# shield.net
KiCad netlist of a schematic drawn in EAGLE
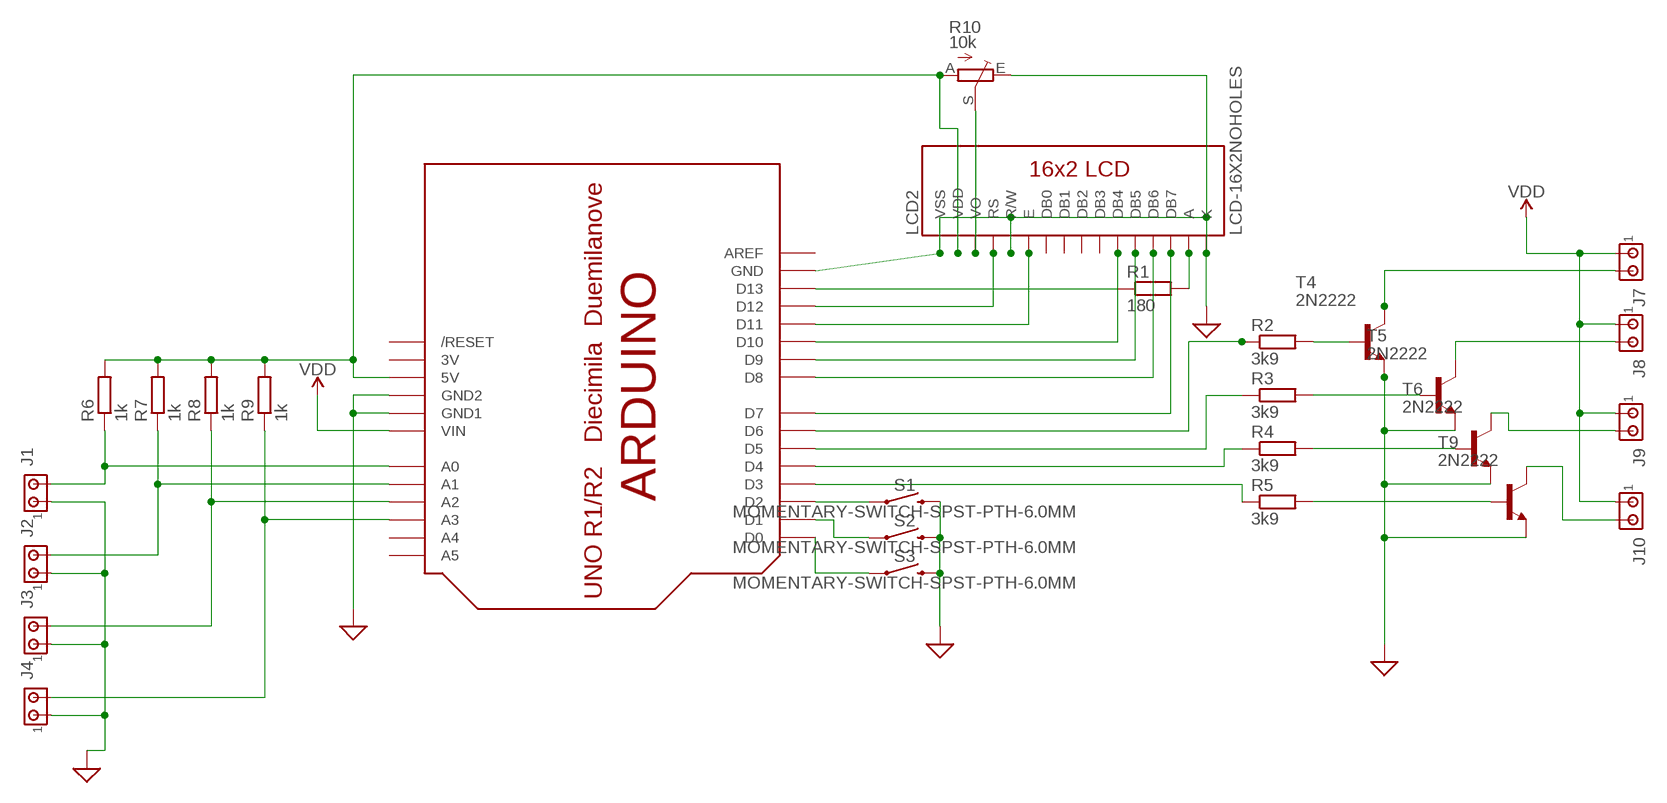
[diagram p0: schematic, sheet 1]

(export (version "E")
  (design (tool "Eeschema 10.0.6"))
  (components
    (comp (ref "J1")
      (value "MTA02-100")
      (footprint "eagle-import:10X02MTA")
      (libsource (lib "eagle-import") (part "MTA02-100"))
    )
    (comp (ref "J2")
      (value "MTA02-100")
      (footprint "eagle-import:10X02MTA")
      (libsource (lib "eagle-import") (part "MTA02-100"))
    )
    (comp (ref "J3")
      (value "MTA02-100")
      (footprint "eagle-import:10X02MTA")
      (libsource (lib "eagle-import") (part "MTA02-100"))
    )
    (comp (ref "J4")
      (value "MTA02-100")
      (footprint "eagle-import:10X02MTA")
      (libsource (lib "eagle-import") (part "MTA02-100"))
    )
    (comp (ref "J7")
      (value "MTA02-100")
      (footprint "eagle-import:10X02MTA")
      (libsource (lib "eagle-import") (part "MTA02-100"))
    )
    (comp (ref "J8")
      (value "MTA02-100")
      (footprint "eagle-import:10X02MTA")
      (libsource (lib "eagle-import") (part "MTA02-100"))
    )
    (comp (ref "J9")
      (value "MTA02-100")
      (footprint "eagle-import:10X02MTA")
      (libsource (lib "eagle-import") (part "MTA02-100"))
    )
    (comp (ref "J10")
      (value "MTA02-100")
      (footprint "eagle-import:10X02MTA")
      (libsource (lib "eagle-import") (part "MTA02-100"))
    )
    (comp (ref "LCD2")
      (value "LCD-16X2NOHOLES")
      (footprint "eagle-import:LCD-16X2_NOHOLESNOSILK")
      (libsource (lib "eagle-import") (part "LCD-16X2NOHOLES"))
    )
    (comp (ref "R1")
      (value "180")
      (footprint "eagle-import:0207_10")
      (libsource (lib "eagle-import") (part "R-EU_0207/10"))
    )
    (comp (ref "R2")
      (value "3k9")
      (footprint "eagle-import:0207_10")
      (libsource (lib "eagle-import") (part "R-EU_0207/10"))
    )
    (comp (ref "R3")
      (value "3k9")
      (footprint "eagle-import:0207_10")
      (libsource (lib "eagle-import") (part "R-EU_0207/10"))
    )
    (comp (ref "R4")
      (value "3k9")
      (footprint "eagle-import:0207_10")
      (libsource (lib "eagle-import") (part "R-EU_0207/10"))
    )
    (comp (ref "R5")
      (value "3k9")
      (footprint "eagle-import:0207_10")
      (libsource (lib "eagle-import") (part "R-EU_0207/10"))
    )
    (comp (ref "R6")
      (value "1k")
      (footprint "eagle-import:0207_10")
      (libsource (lib "eagle-import") (part "R-EU_0207/10"))
    )
    (comp (ref "R7")
      (value "1k")
      (footprint "eagle-import:0207_10")
      (libsource (lib "eagle-import") (part "R-EU_0207/10"))
    )
    (comp (ref "R8")
      (value "1k")
      (footprint "eagle-import:0207_10")
      (libsource (lib "eagle-import") (part "R-EU_0207/10"))
    )
    (comp (ref "R9")
      (value "1k")
      (footprint "eagle-import:0207_10")
      (libsource (lib "eagle-import") (part "R-EU_0207/10"))
    )
    (comp (ref "R10")
      (value "10k")
      (footprint "eagle-import:B25P")
      (libsource (lib "eagle-import") (part "TRIM_EU-B25P"))
    )
    (comp (ref "S1")
      (value "MOMENTARY-SWITCH-SPST-PTH-6.0MM")
      (footprint "eagle-import:TACTILE_SWITCH_PTH_6.0MM")
      (libsource (lib "eagle-import") (part "MOMENTARY-SWITCH-SPST-PTH-6.0MM"))
    )
    (comp (ref "S2")
      (value "MOMENTARY-SWITCH-SPST-PTH-6.0MM")
      (footprint "eagle-import:TACTILE_SWITCH_PTH_6.0MM")
      (libsource (lib "eagle-import") (part "MOMENTARY-SWITCH-SPST-PTH-6.0MM"))
    )
    (comp (ref "S3")
      (value "MOMENTARY-SWITCH-SPST-PTH-6.0MM")
      (footprint "eagle-import:TACTILE_SWITCH_PTH_6.0MM")
      (libsource (lib "eagle-import") (part "MOMENTARY-SWITCH-SPST-PTH-6.0MM"))
    )
    (comp (ref "T4")
      (value "2N2222")
      (footprint "eagle-import:TO92-EBC-OVAL")
      (libsource (lib "eagle-import") (part "2N2222"))
    )
    (comp (ref "T5")
      (value "2N2222")
      (footprint "eagle-import:TO92-EBC-OVAL")
      (libsource (lib "eagle-import") (part "2N2222"))
    )
    (comp (ref "T6")
      (value "2N2222")
      (footprint "eagle-import:TO92-EBC-OVAL")
      (libsource (lib "eagle-import") (part "2N2222"))
    )
    (comp (ref "T9")
      (value "2N2222")
      (footprint "eagle-import:TO92-EBC-OVAL")
      (libsource (lib "eagle-import") (part "2N2222"))
    )
    (comp (ref "U$1")
      (value "ARDUINO-NOHOLE")
      (footprint "eagle-import:ARDUINO-NOHOLE")
      (libsource (lib "eagle-import") (part "ARDUINO-NOHOLE"))
    )
  )
  (nets
    (net (code "1") (name "/3V") (class "Default")
      (node (ref "U$1") (pin "3V") (pinfunction "3V_3V") (pintype "power_in"))
    )
    (net (code "2") (name "Net-(J1-Pad2)") (class "Default")
      (node (ref "J1") (pin "2") (pinfunction "2_2") (pintype "passive"))
      (node (ref "R6") (pin "1") (pinfunction "1_1") (pintype "passive"))
      (node (ref "U$1") (pin "A0") (pinfunction "A0_A0") (pintype "bidirectional"))
    )
    (net (code "3") (name "Net-(J2-Pad2)") (class "Default")
      (node (ref "J2") (pin "2") (pinfunction "2_2") (pintype "passive"))
      (node (ref "R7") (pin "1") (pinfunction "1_1") (pintype "passive"))
      (node (ref "U$1") (pin "A1") (pinfunction "A1_A1") (pintype "bidirectional"))
    )
    (net (code "4") (name "Net-(J3-Pad2)") (class "Default")
      (node (ref "J3") (pin "2") (pinfunction "2_2") (pintype "passive"))
      (node (ref "R8") (pin "1") (pinfunction "1_1") (pintype "passive"))
      (node (ref "U$1") (pin "A2") (pinfunction "A2_A2") (pintype "bidirectional"))
    )
    (net (code "5") (name "Net-(J4-Pad2)") (class "Default")
      (node (ref "J4") (pin "2") (pinfunction "2_2") (pintype "passive"))
      (node (ref "R9") (pin "1") (pinfunction "1_1") (pintype "passive"))
      (node (ref "U$1") (pin "A3") (pinfunction "A3_A3") (pintype "bidirectional"))
    )
    (net (code "6") (name "Net-(J7-Pad2)") (class "Default")
      (node (ref "J7") (pin "2") (pinfunction "2_2") (pintype "passive"))
      (node (ref "T4") (pin "C") (pinfunction "C_C") (pintype "passive"))
    )
    (net (code "7") (name "Net-(J8-Pad2)") (class "Default")
      (node (ref "J8") (pin "2") (pinfunction "2_2") (pintype "passive"))
      (node (ref "T5") (pin "C") (pinfunction "C_C") (pintype "passive"))
    )
    (net (code "8") (name "Net-(J9-Pad2)") (class "Default")
      (node (ref "J9") (pin "2") (pinfunction "2_2") (pintype "passive"))
      (node (ref "T6") (pin "C") (pinfunction "C_C") (pintype "passive"))
    )
    (net (code "9") (name "Net-(J10-Pad2)") (class "Default")
      (node (ref "J10") (pin "2") (pinfunction "2_2") (pintype "passive"))
      (node (ref "T9") (pin "C") (pinfunction "C_C") (pintype "passive"))
    )
    (net (code "10") (name "Net-(LCD2-A)") (class "Default")
      (node (ref "LCD2") (pin "15") (pinfunction "A_15") (pintype "power_in"))
      (node (ref "R1") (pin "2") (pinfunction "2_2") (pintype "passive"))
    )
    (net (code "11") (name "Net-(LCD2-DB4)") (class "Default")
      (node (ref "LCD2") (pin "11") (pinfunction "DB4_11") (pintype "bidirectional"))
      (node (ref "U$1") (pin "D10") (pinfunction "D10_D10") (pintype "bidirectional"))
    )
    (net (code "12") (name "Net-(LCD2-DB5)") (class "Default")
      (node (ref "LCD2") (pin "12") (pinfunction "DB5_12") (pintype "bidirectional"))
      (node (ref "U$1") (pin "D9") (pinfunction "D9_D9") (pintype "bidirectional"))
    )
    (net (code "13") (name "Net-(LCD2-DB6)") (class "Default")
      (node (ref "LCD2") (pin "13") (pinfunction "DB6_13") (pintype "bidirectional"))
      (node (ref "U$1") (pin "D8") (pinfunction "D8_D8") (pintype "bidirectional"))
    )
    (net (code "14") (name "Net-(LCD2-DB7)") (class "Default")
      (node (ref "LCD2") (pin "14") (pinfunction "DB7_14") (pintype "bidirectional"))
      (node (ref "U$1") (pin "D7") (pinfunction "D7_D7") (pintype "bidirectional"))
    )
    (net (code "15") (name "Net-(LCD2-E)") (class "Default")
      (node (ref "LCD2") (pin "6") (pinfunction "E_6") (pintype "input"))
      (node (ref "U$1") (pin "D11") (pinfunction "D11_D11") (pintype "bidirectional"))
    )
    (net (code "16") (name "Net-(LCD2-RS)") (class "Default")
      (node (ref "LCD2") (pin "4") (pinfunction "RS_4") (pintype "input"))
      (node (ref "U$1") (pin "D12") (pinfunction "D12_D12") (pintype "bidirectional"))
    )
    (net (code "17") (name "Net-(LCD2-VDD)") (class "Default")
      (node (ref "LCD2") (pin "2") (pinfunction "VDD_2") (pintype "power_in"))
      (node (ref "R10") (pin "A") (pinfunction "A_A") (pintype "passive"))
      (node (ref "R6") (pin "2") (pinfunction "2_2") (pintype "passive"))
      (node (ref "R7") (pin "2") (pinfunction "2_2") (pintype "passive"))
      (node (ref "R8") (pin "2") (pinfunction "2_2") (pintype "passive"))
      (node (ref "R9") (pin "2") (pinfunction "2_2") (pintype "passive"))
      (node (ref "U$1") (pin "5V") (pinfunction "5V_5V") (pintype "power_in"))
    )
    (net (code "18") (name "Net-(LCD2-VO)") (class "Default")
      (node (ref "LCD2") (pin "3") (pinfunction "VO_3") (pintype "bidirectional"))
      (node (ref "R10") (pin "S") (pinfunction "S_S") (pintype "passive"))
    )
    (net (code "19") (name "Net-(R1-Pad1)") (class "Default")
      (node (ref "R1") (pin "1") (pinfunction "1_1") (pintype "passive"))
      (node (ref "U$1") (pin "D13") (pinfunction "D13_D13") (pintype "bidirectional"))
    )
    (net (code "20") (name "Net-(R2-Pad1)") (class "Default")
      (node (ref "R2") (pin "1") (pinfunction "1_1") (pintype "passive"))
      (node (ref "U$1") (pin "D6") (pinfunction "D6_D6") (pintype "bidirectional"))
    )
    (net (code "21") (name "Net-(R2-Pad2)") (class "Default")
      (node (ref "R2") (pin "2") (pinfunction "2_2") (pintype "passive"))
      (node (ref "T4") (pin "B") (pinfunction "B_B") (pintype "passive"))
    )
    (net (code "22") (name "Net-(R3-Pad1)") (class "Default")
      (node (ref "R3") (pin "1") (pinfunction "1_1") (pintype "passive"))
      (node (ref "U$1") (pin "D5") (pinfunction "D5_D5") (pintype "bidirectional"))
    )
    (net (code "23") (name "Net-(R3-Pad2)") (class "Default")
      (node (ref "R3") (pin "2") (pinfunction "2_2") (pintype "passive"))
      (node (ref "T5") (pin "B") (pinfunction "B_B") (pintype "passive"))
    )
    (net (code "24") (name "Net-(R4-Pad1)") (class "Default")
      (node (ref "R4") (pin "1") (pinfunction "1_1") (pintype "passive"))
      (node (ref "U$1") (pin "D4") (pinfunction "D4_D4") (pintype "bidirectional"))
    )
    (net (code "25") (name "Net-(R4-Pad2)") (class "Default")
      (node (ref "R4") (pin "2") (pinfunction "2_2") (pintype "passive"))
      (node (ref "T6") (pin "B") (pinfunction "B_B") (pintype "passive"))
    )
    (net (code "26") (name "Net-(R5-Pad1)") (class "Default")
      (node (ref "R5") (pin "1") (pinfunction "1_1") (pintype "passive"))
      (node (ref "U$1") (pin "D3") (pinfunction "D3_D3") (pintype "bidirectional"))
    )
    (net (code "27") (name "Net-(R5-Pad2)") (class "Default")
      (node (ref "R5") (pin "2") (pinfunction "2_2") (pintype "passive"))
      (node (ref "T9") (pin "B") (pinfunction "B_B") (pintype "passive"))
    )
    (net (code "28") (name "Net-(S1-Pad1)") (class "Default")
      (node (ref "S1") (pin "1") (pinfunction "1_1") (pintype "passive"))
      (node (ref "U$1") (pin "D2") (pinfunction "D2_D2") (pintype "bidirectional"))
    )
    (net (code "29") (name "Net-(S2-Pad1)") (class "Default")
      (node (ref "S2") (pin "1") (pinfunction "1_1") (pintype "passive"))
      (node (ref "U$1") (pin "D1") (pinfunction "D1_D1") (pintype "bidirectional"))
    )
    (net (code "30") (name "Net-(S3-Pad1)") (class "Default")
      (node (ref "S3") (pin "1") (pinfunction "1_1") (pintype "passive"))
      (node (ref "U$1") (pin "D0") (pinfunction "D0_D0") (pintype "bidirectional"))
    )
    (net (code "31") (name "SUP") (class "Default")
      (node (ref "J1") (pin "1") (pinfunction "1_1") (pintype "passive"))
      (node (ref "J2") (pin "1") (pinfunction "1_1") (pintype "passive"))
      (node (ref "J3") (pin "1") (pinfunction "1_1") (pintype "passive"))
      (node (ref "J4") (pin "1") (pinfunction "1_1") (pintype "passive"))
      (node (ref "LCD2") (pin "1") (pinfunction "VSS_1") (pintype "power_in"))
      (node (ref "LCD2") (pin "16") (pinfunction "K_16") (pintype "power_in"))
      (node (ref "LCD2") (pin "5") (pinfunction "R/W_5") (pintype "input"))
      (node (ref "R10") (pin "E") (pinfunction "E_E") (pintype "passive"))
      (node (ref "S1") (pin "3") (pinfunction "2_3") (pintype "passive"))
      (node (ref "S2") (pin "3") (pinfunction "2_3") (pintype "passive"))
      (node (ref "S3") (pin "3") (pinfunction "2_3") (pintype "passive"))
      (node (ref "T4") (pin "E") (pinfunction "E_E") (pintype "passive"))
      (node (ref "T5") (pin "E") (pinfunction "E_E") (pintype "passive"))
      (node (ref "T6") (pin "E") (pinfunction "E_E") (pintype "passive"))
      (node (ref "T9") (pin "E") (pinfunction "E_E") (pintype "passive"))
      (node (ref "U$1") (pin "GND") (pinfunction "GND_GND") (pintype "power_in"))
      (node (ref "U$1") (pin "GND1") (pinfunction "GND1_GND1") (pintype "power_in"))
      (node (ref "U$1") (pin "GND2") (pinfunction "GND2_GND2") (pintype "power_in"))
    )
    (net (code "32") (name "VDD") (class "Default")
      (node (ref "J10") (pin "1") (pinfunction "1_1") (pintype "passive"))
      (node (ref "J7") (pin "1") (pinfunction "1_1") (pintype "passive"))
      (node (ref "J8") (pin "1") (pinfunction "1_1") (pintype "passive"))
      (node (ref "J9") (pin "1") (pinfunction "1_1") (pintype "passive"))
      (node (ref "U$1") (pin "VIN") (pinfunction "VIN_VIN") (pintype "power_in"))
    )
    (net (code "33") (name "unconnected-(LCD2-DB0-Pad7)") (class "Default")
      (node (ref "LCD2") (pin "7") (pinfunction "DB0_7") (pintype "bidirectional"))
    )
    (net (code "34") (name "unconnected-(LCD2-DB1-Pad8)") (class "Default")
      (node (ref "LCD2") (pin "8") (pinfunction "DB1_8") (pintype "bidirectional"))
    )
    (net (code "35") (name "unconnected-(LCD2-DB2-Pad9)") (class "Default")
      (node (ref "LCD2") (pin "9") (pinfunction "DB2_9") (pintype "bidirectional"))
    )
    (net (code "36") (name "unconnected-(LCD2-DB3-Pad10)") (class "Default")
      (node (ref "LCD2") (pin "10") (pinfunction "DB3_10") (pintype "bidirectional"))
    )
    (net (code "37") (name "unconnected-(U$1-PadA4)") (class "Default")
      (node (ref "U$1") (pin "A4") (pinfunction "A4_A4") (pintype "bidirectional"))
    )
    (net (code "38") (name "unconnected-(U$1-PadA5)") (class "Default")
      (node (ref "U$1") (pin "A5") (pinfunction "A5_A5") (pintype "bidirectional"))
    )
    (net (code "39") (name "unconnected-(U$1-PadAREF)") (class "Default")
      (node (ref "U$1") (pin "AREF") (pinfunction "AREF_AREF") (pintype "bidirectional"))
    )
    (net (code "40") (name "unconnected-(U$1-{slash}RESET-PadRESET)") (class "Default")
      (node (ref "U$1") (pin "RESET") (pinfunction "/RESET_RESET") (pintype "bidirectional"))
    )
  )
)
